# socket-v2-high-voltage.net
KiCad netlist of a schematic drawn in EAGLE
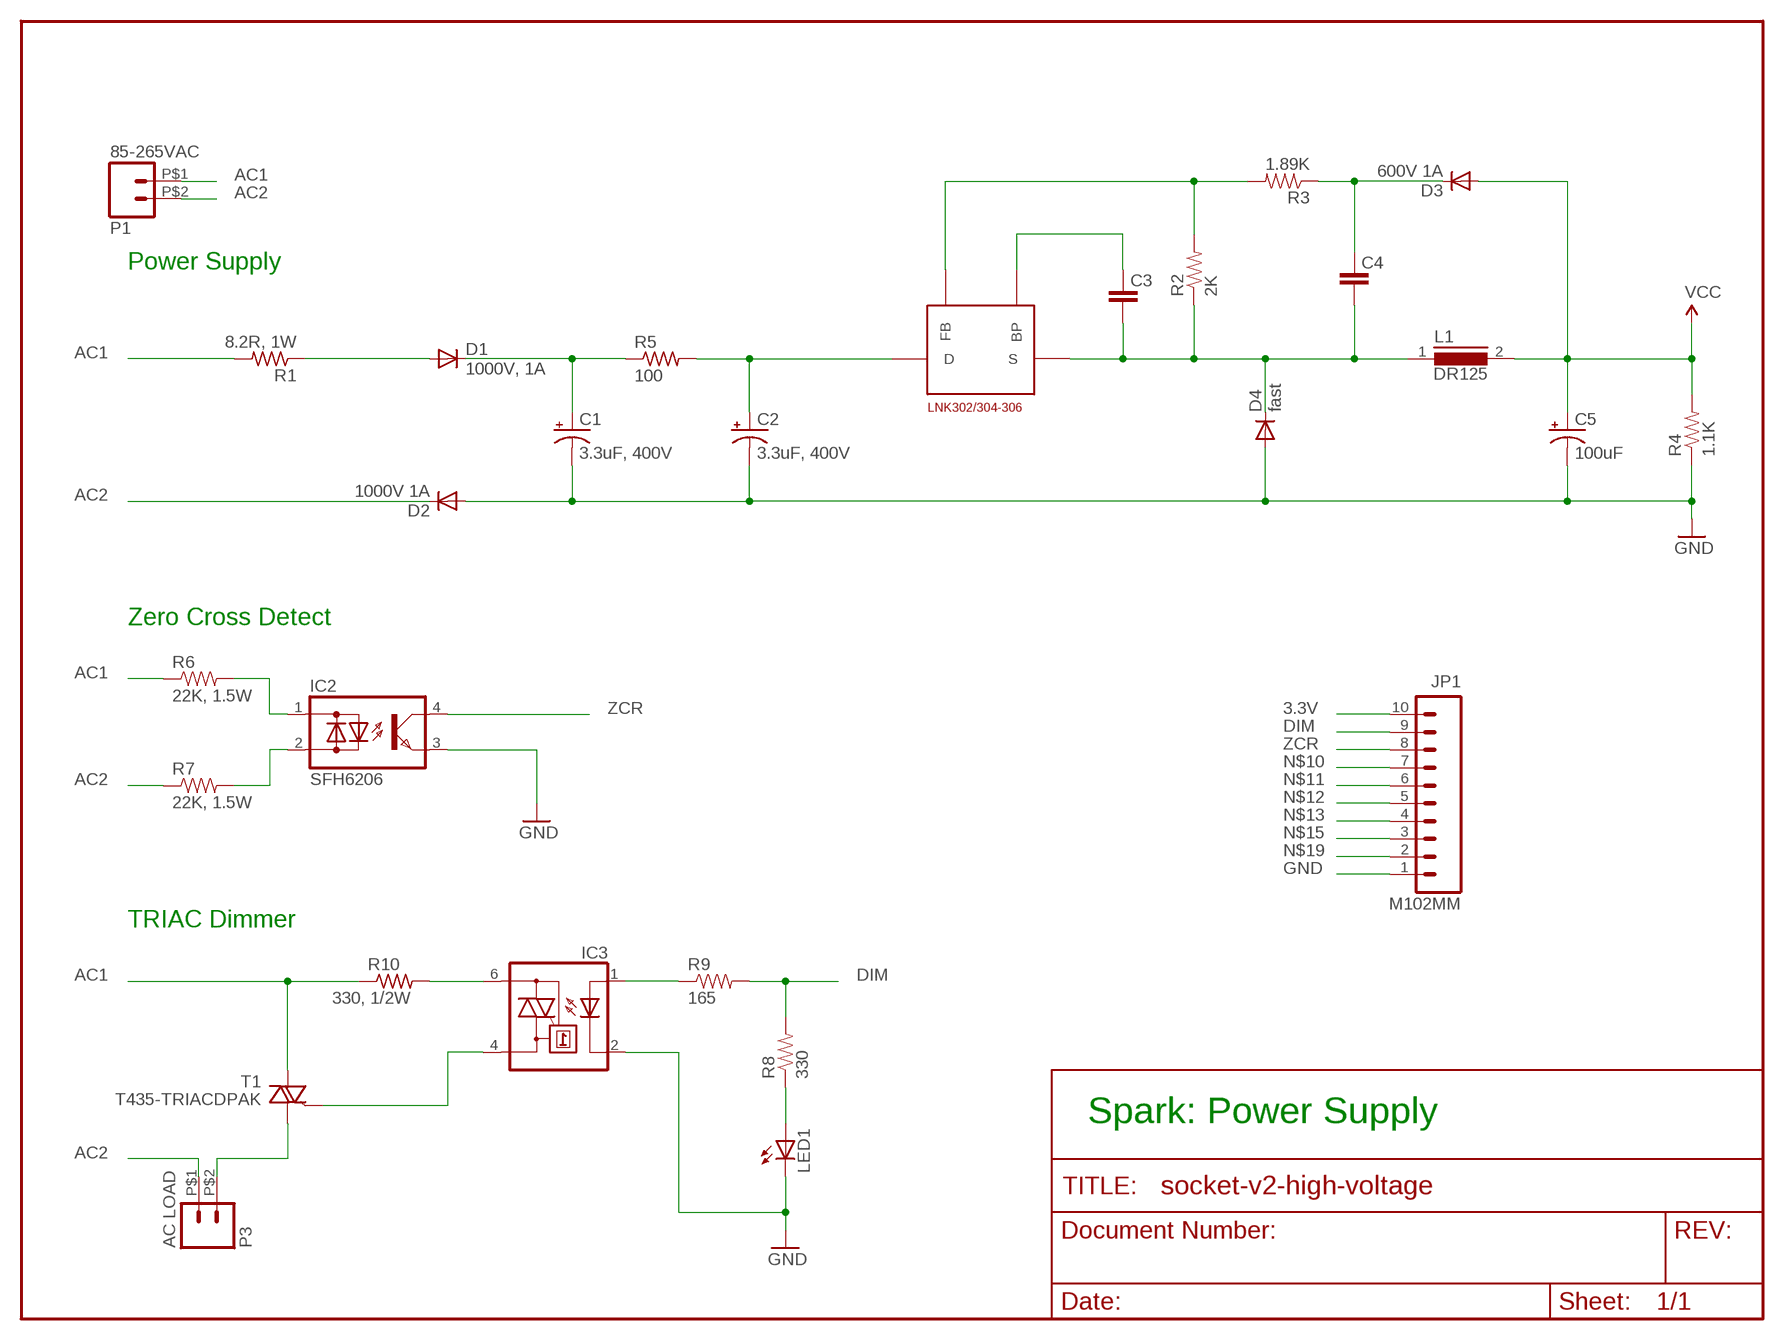
[diagram p0: schematic, sheet 1]

(export (version "E")
  (design (tool "Eeschema 10.0.6"))
  (components
    (comp (ref "C1")
      (value "3.3uF, 400V")
      (footprint "eagle-import:E3,5-8")
      (libsource (lib "eagle-import") (part "CPOL-USE3.5-8"))
    )
    (comp (ref "C2")
      (value "3.3uF, 400V")
      (footprint "eagle-import:E3,5-8")
      (libsource (lib "eagle-import") (part "CPOL-USE3.5-8"))
    )
    (comp (ref "C3")
      (value "0.1uF")
      (footprint "eagle-import:0603-CAP")
      (libsource (lib "eagle-import") (part "CAP0603-CAP"))
    )
    (comp (ref "C4")
      (value "10uF, 50V")
      (footprint "eagle-import:0805")
      (libsource (lib "eagle-import") (part "CAP0805"))
    )
    (comp (ref "C5")
      (value "100uF")
      (footprint "eagle-import:EIA3528")
      (libsource (lib "eagle-import") (part "CAP_POL3528"))
    )
    (comp (ref "D1")
      (value "1000V, 1A")
      (footprint "eagle-import:SMA-DIODE")
      (libsource (lib "eagle-import") (part "DIODESMA"))
    )
    (comp (ref "D2")
      (value "1000V 1A")
      (footprint "eagle-import:SMA-DIODE")
      (libsource (lib "eagle-import") (part "DIODESMA"))
    )
    (comp (ref "D3")
      (value "600V 1A")
      (footprint "eagle-import:SMA-DIODE")
      (libsource (lib "eagle-import") (part "DIODESMA"))
    )
    (comp (ref "D4")
      (value "fast")
      (footprint "eagle-import:SMA-DIODE")
      (libsource (lib "eagle-import") (part "DIODESMA"))
    )
    (comp (ref "IC1")
      (value "LNK302/304-306")
      (footprint "eagle-import:SMD-8B")
      (libsource (lib "eagle-import") (part "LNK302/304-306"))
    )
    (comp (ref "IC2")
      (value "SFH6206")
      (footprint "eagle-import:DIL4-SMD")
      (fields (field (name "MF") "VISHAY/TELEFUNKEN") (field (name "MPN") "SFH6206-3"))
      (libsource (lib "eagle-import") (part "SFH6206"))
    )
    (comp (ref "IC3")
      (value "MOC3031S")
      (footprint "eagle-import:DIL6-SMD")
      (fields
        (field (name "MF") "FAIRCHILD SEMICONDUCTOR")
        (field (name "MPN") "MOC3031SM")
        (field (name "MPN_1") "MOC3031SM")
        (field (name "OC_FARNELL") "unknown")
        (field (name "OC_NEWARK") "34C1335")
      )
      (libsource (lib "eagle-import") (part "MOC30S31"))
    )
    (comp (ref "JP1")
      (value "M102MM")
      (footprint "eagle-import:1X10-2MM")
      (libsource (lib "eagle-import") (part "M102MM"))
    )
    (comp (ref "L1")
      (value "DR125")
      (footprint "eagle-import:DR125")
      (libsource (lib "eagle-import") (part "DR125"))
    )
    (comp (ref "LED1")
      (value "LED0603")
      (footprint "eagle-import:LED-0603")
      (libsource (lib "eagle-import") (part "LED0603"))
    )
    (comp (ref "P1")
      (value "85-265VAC")
      (footprint "eagle-import:1X02_BIG")
      (libsource (lib "eagle-import") (part "M02PTH2"))
    )
    (comp (ref "P3")
      (value "AC LOAD")
      (footprint "eagle-import:1X02_BIG")
      (libsource (lib "eagle-import") (part "M02PTH2"))
    )
    (comp (ref "R1")
      (value "8.2R, 1W")
      (footprint "eagle-import:0207_10")
      (libsource (lib "eagle-import") (part "R-US_0207/10"))
    )
    (comp (ref "R2")
      (value "2K")
      (footprint "eagle-import:0805")
      (libsource (lib "eagle-import") (part "RESISTOR0805-RES"))
    )
    (comp (ref "R3")
      (value "1.89K")
      (footprint "eagle-import:0805")
      (libsource (lib "eagle-import") (part "RESISTOR0805-RES"))
    )
    (comp (ref "R4")
      (value "1.1K")
      (footprint "eagle-import:0603-RES")
      (libsource (lib "eagle-import") (part "RESISTOR0603-RES"))
    )
    (comp (ref "R5")
      (value "100")
      (footprint "eagle-import:0204_7")
      (libsource (lib "eagle-import") (part "R-US_0204/7"))
    )
    (comp (ref "R6")
      (value "22K, 1.5W")
      (footprint "eagle-import:R2512")
      (libsource (lib "eagle-import") (part "RESISTOR2512"))
    )
    (comp (ref "R7")
      (value "22K, 1.5W")
      (footprint "eagle-import:R2512")
      (libsource (lib "eagle-import") (part "RESISTOR2512"))
    )
    (comp (ref "R8")
      (value "330")
      (footprint "eagle-import:0805")
      (libsource (lib "eagle-import") (part "RESISTOR0805-RES"))
    )
    (comp (ref "R9")
      (value "165")
      (footprint "eagle-import:0805")
      (libsource (lib "eagle-import") (part "RESISTOR0805-RES"))
    )
    (comp (ref "R10")
      (value "330, 1/2W")
      (footprint "eagle-import:R1210")
      (libsource (lib "eagle-import") (part "R-US_R1210"))
    )
    (comp (ref "T1")
      (value "T435-TRIACDPAK")
      (footprint "eagle-import:TO252")
      (libsource (lib "eagle-import") (part "T435-TRIACDPAK"))
    )
  )
  (nets
    (net (code "1") (name "/AC1") (class "Default")
      (node (ref "P1") (pin "P$1") (pinfunction "1_P$1") (pintype "passive"))
      (node (ref "R1") (pin "2") (pinfunction "2_2") (pintype "passive"))
      (node (ref "R10") (pin "1") (pinfunction "1_1") (pintype "passive"))
      (node (ref "R6") (pin "1") (pinfunction "1_1") (pintype "passive"))
      (node (ref "T1") (pin "2") (pinfunction "A2_2") (pintype "passive"))
    )
    (net (code "2") (name "/AC2") (class "Default")
      (node (ref "D2") (pin "C") (pinfunction "C_C") (pintype "passive"))
      (node (ref "P1") (pin "P$2") (pinfunction "2_P$2") (pintype "passive"))
      (node (ref "P3") (pin "P$1") (pinfunction "1_P$1") (pintype "passive"))
      (node (ref "R7") (pin "1") (pinfunction "1_1") (pintype "passive"))
    )
    (net (code "3") (name "/DIM") (class "Default")
      (node (ref "JP1") (pin "9") (pinfunction "9_9") (pintype "passive"))
      (node (ref "R8") (pin "2") (pinfunction "2_2") (pintype "passive"))
      (node (ref "R9") (pin "2") (pinfunction "2_2") (pintype "passive"))
    )
    (net (code "4") (name "/N$10") (class "Default")
      (node (ref "JP1") (pin "7") (pinfunction "7_7") (pintype "passive"))
    )
    (net (code "5") (name "/N$11") (class "Default")
      (node (ref "JP1") (pin "6") (pinfunction "6_6") (pintype "passive"))
    )
    (net (code "6") (name "/N$12") (class "Default")
      (node (ref "JP1") (pin "5") (pinfunction "5_5") (pintype "passive"))
    )
    (net (code "7") (name "/N$13") (class "Default")
      (node (ref "JP1") (pin "4") (pinfunction "4_4") (pintype "passive"))
    )
    (net (code "8") (name "/N$15") (class "Default")
      (node (ref "JP1") (pin "3") (pinfunction "3_3") (pintype "passive"))
    )
    (net (code "9") (name "/N$19") (class "Default")
      (node (ref "JP1") (pin "2") (pinfunction "2_2") (pintype "passive"))
    )
    (net (code "10") (name "/ZCR") (class "Default")
      (node (ref "IC2") (pin "4") (pinfunction "C_4") (pintype "passive"))
      (node (ref "JP1") (pin "8") (pinfunction "8_8") (pintype "passive"))
    )
    (net (code "11") (name "GND") (class "Default")
      (node (ref "C1") (pin "-") (pinfunction "-_-") (pintype "passive"))
      (node (ref "C2") (pin "-") (pinfunction "-_-") (pintype "passive"))
      (node (ref "C5") (pin "C") (pinfunction "-_C") (pintype "passive"))
      (node (ref "D2") (pin "A") (pinfunction "A_A") (pintype "passive"))
      (node (ref "D4") (pin "A") (pinfunction "A_A") (pintype "passive"))
      (node (ref "IC2") (pin "3") (pinfunction "E_3") (pintype "passive"))
      (node (ref "IC3") (pin "2") (pinfunction "C_2") (pintype "passive"))
      (node (ref "JP1") (pin "1") (pinfunction "1_1") (pintype "passive"))
      (node (ref "LED1") (pin "C") (pinfunction "C_C") (pintype "passive"))
      (node (ref "R4") (pin "1") (pinfunction "1_1") (pintype "passive"))
    )
    (net (code "12") (name "Net-(C1-Pad+)") (class "Default")
      (node (ref "C1") (pin "+") (pinfunction "+_+") (pintype "passive"))
      (node (ref "D1") (pin "C") (pinfunction "C_C") (pintype "passive"))
      (node (ref "R5") (pin "1") (pinfunction "1_1") (pintype "passive"))
    )
    (net (code "13") (name "Net-(C2-Pad+)") (class "Default")
      (node (ref "C2") (pin "+") (pinfunction "+_+") (pintype "passive"))
      (node (ref "IC1") (pin "D") (pinfunction "D_D") (pintype "bidirectional"))
      (node (ref "R5") (pin "2") (pinfunction "2_2") (pintype "passive"))
    )
    (net (code "14") (name "Net-(C3-Pad2)") (class "Default")
      (node (ref "C3") (pin "2") (pinfunction "2_2") (pintype "passive"))
      (node (ref "IC1") (pin "BP") (pinfunction "BP_BP") (pintype "bidirectional"))
    )
    (net (code "15") (name "Net-(C4-Pad2)") (class "Default")
      (node (ref "C4") (pin "2") (pinfunction "2_2") (pintype "passive"))
      (node (ref "D3") (pin "C") (pinfunction "C_C") (pintype "passive"))
      (node (ref "R3") (pin "1") (pinfunction "1_1") (pintype "passive"))
    )
    (net (code "16") (name "Net-(D1-PadA)") (class "Default")
      (node (ref "D1") (pin "A") (pinfunction "A_A") (pintype "passive"))
      (node (ref "R1") (pin "1") (pinfunction "1_1") (pintype "passive"))
    )
    (net (code "17") (name "Net-(IC1-PadFB)") (class "Default")
      (node (ref "IC1") (pin "FB") (pinfunction "FB_FB") (pintype "bidirectional"))
      (node (ref "R2") (pin "2") (pinfunction "2_2") (pintype "passive"))
      (node (ref "R3") (pin "2") (pinfunction "2_2") (pintype "passive"))
    )
    (net (code "18") (name "Net-(IC1-S)") (class "Default")
      (node (ref "C3") (pin "1") (pinfunction "1_1") (pintype "passive"))
      (node (ref "C4") (pin "1") (pinfunction "1_1") (pintype "passive"))
      (node (ref "D4") (pin "C") (pinfunction "C_C") (pintype "passive"))
      (node (ref "IC1") (pin "S1") (pinfunction "S_S1") (pintype "bidirectional"))
      (node (ref "L1") (pin "1") (pinfunction "1_1") (pintype "passive"))
      (node (ref "R2") (pin "1") (pinfunction "1_1") (pintype "passive"))
    )
    (net (code "19") (name "Net-(IC2-AC1)") (class "Default")
      (node (ref "IC2") (pin "1") (pinfunction "AC1_1") (pintype "passive"))
      (node (ref "R6") (pin "2") (pinfunction "2_2") (pintype "passive"))
    )
    (net (code "20") (name "Net-(IC2-AC2)") (class "Default")
      (node (ref "IC2") (pin "2") (pinfunction "AC2_2") (pintype "passive"))
      (node (ref "R7") (pin "2") (pinfunction "2_2") (pintype "passive"))
    )
    (net (code "21") (name "Net-(IC3-A)") (class "Default")
      (node (ref "IC3") (pin "1") (pinfunction "A_1") (pintype "passive"))
      (node (ref "R9") (pin "1") (pinfunction "1_1") (pintype "passive"))
    )
    (net (code "22") (name "Net-(IC3-A1)") (class "Default")
      (node (ref "IC3") (pin "4") (pinfunction "A1_4") (pintype "passive"))
      (node (ref "T1") (pin "3") (pinfunction "G_3") (pintype "passive"))
    )
    (net (code "23") (name "Net-(IC3-A2)") (class "Default")
      (node (ref "IC3") (pin "6") (pinfunction "A2_6") (pintype "passive"))
      (node (ref "R10") (pin "2") (pinfunction "2_2") (pintype "passive"))
    )
    (net (code "24") (name "Net-(LED1-PadA)") (class "Default")
      (node (ref "LED1") (pin "A") (pinfunction "A_A") (pintype "passive"))
      (node (ref "R8") (pin "1") (pinfunction "1_1") (pintype "passive"))
    )
    (net (code "25") (name "Net-(P3-2)") (class "Default")
      (node (ref "P3") (pin "P$2") (pinfunction "2_P$2") (pintype "passive"))
      (node (ref "T1") (pin "1") (pinfunction "A1_1") (pintype "passive"))
    )
    (net (code "26") (name "VCC") (class "Default")
      (node (ref "C5") (pin "A") (pinfunction "+_A") (pintype "passive"))
      (node (ref "D3") (pin "A") (pinfunction "A_A") (pintype "passive"))
      (node (ref "JP1") (pin "10") (pinfunction "10_10") (pintype "passive"))
      (node (ref "L1") (pin "2") (pinfunction "2_2") (pintype "passive"))
      (node (ref "R4") (pin "2") (pinfunction "2_2") (pintype "passive"))
    )
  )
)
